# ESP-XBee_v1_0.net
KiCad netlist of a schematic drawn in EAGLE
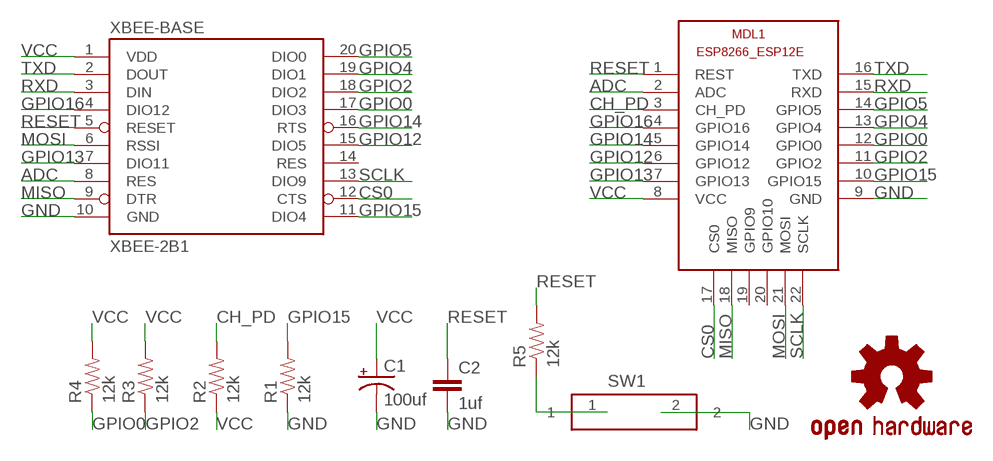
[diagram p0: schematic, sheet 1]

(export (version "E")
  (design (tool "Eeschema 10.0.6"))
  (components
    (comp (ref "C1")
      (value "100uf")
      (footprint "eagle-import:EIA3216-KIT")
      (libsource (lib "eagle-import") (part "CAP_POL1206-KIT"))
    )
    (comp (ref "C2")
      (value "1uf")
      (footprint "eagle-import:0805")
      (libsource (lib "eagle-import") (part "CAP0805"))
    )
    (comp (ref "LOGO3")
      (value "OSHW-LOGOS")
      (footprint "eagle-import:OSHW-LOGO-S")
      (libsource (lib "eagle-import") (part "OSHW-LOGOS"))
    )
    (comp (ref "MDL1")
      (value "ESP8266-12EESP8266-ESP12E")
      (footprint "eagle-import:ESP8266-ESP12E")
      (libsource (lib "eagle-import") (part "ESP8266-12EESP8266-ESP12E"))
    )
    (comp (ref "R1")
      (value "12k")
      (footprint "eagle-import:0805")
      (libsource (lib "eagle-import") (part "RESISTOR0805-RES"))
    )
    (comp (ref "R2")
      (value "12k")
      (footprint "eagle-import:0805")
      (libsource (lib "eagle-import") (part "RESISTOR0805-RES"))
    )
    (comp (ref "R3")
      (value "12k")
      (footprint "eagle-import:0805")
      (libsource (lib "eagle-import") (part "RESISTOR0805-RES"))
    )
    (comp (ref "R4")
      (value "12k")
      (footprint "eagle-import:0805")
      (libsource (lib "eagle-import") (part "RESISTOR0805-RES"))
    )
    (comp (ref "R5")
      (value "12k")
      (footprint "eagle-import:0805")
      (libsource (lib "eagle-import") (part "RESISTOR0805-RES"))
    )
    (comp (ref "SW1")
      (value "434111043826")
      (footprint "eagle-import:434111043826")
      (libsource (lib "eagle-import") (part "434111043826"))
    )
    (comp (ref "XBEE-BASE")
      (value "XBEE-2B1")
      (footprint "eagle-import:XBEE-1")
      (libsource (lib "eagle-import") (part "XBEE-2B1"))
    )
  )
  (nets
    (net (code "1") (name "/ADC") (class "Default")
      (node (ref "MDL1") (pin "2") (pinfunction "ADC_2") (pintype "bidirectional"))
      (node (ref "XBEE-BASE") (pin "8") (pinfunction "RES_8") (pintype "bidirectional"))
    )
    (net (code "2") (name "/CH_PD") (class "Default")
      (node (ref "MDL1") (pin "3") (pinfunction "CH_PD_3") (pintype "bidirectional"))
      (node (ref "R2") (pin "2") (pinfunction "2_2") (pintype "passive"))
    )
    (net (code "3") (name "/CS0") (class "Default")
      (node (ref "MDL1") (pin "17") (pinfunction "CS0_17") (pintype "bidirectional"))
      (node (ref "XBEE-BASE") (pin "12") (pinfunction "CTS_12") (pintype "output"))
    )
    (net (code "4") (name "/GND") (class "Default")
      (node (ref "C1") (pin "C") (pinfunction "-_C") (pintype "passive"))
      (node (ref "C2") (pin "2") (pinfunction "2_2") (pintype "passive"))
      (node (ref "MDL1") (pin "9") (pinfunction "GND_9") (pintype "bidirectional"))
      (node (ref "R1") (pin "1") (pinfunction "1_1") (pintype "passive"))
      (node (ref "SW1") (pin "2") (pinfunction "2_2") (pintype "bidirectional"))
      (node (ref "XBEE-BASE") (pin "10") (pinfunction "GND_10") (pintype "power_in"))
    )
    (net (code "5") (name "/GPIO0") (class "Default")
      (node (ref "MDL1") (pin "12") (pinfunction "GPIO0_12") (pintype "bidirectional"))
      (node (ref "R4") (pin "1") (pinfunction "1_1") (pintype "passive"))
      (node (ref "XBEE-BASE") (pin "17") (pinfunction "DIO3_17") (pintype "bidirectional"))
    )
    (net (code "6") (name "/GPIO2") (class "Default")
      (node (ref "MDL1") (pin "11") (pinfunction "GPIO2_11") (pintype "bidirectional"))
      (node (ref "R3") (pin "1") (pinfunction "1_1") (pintype "passive"))
      (node (ref "XBEE-BASE") (pin "18") (pinfunction "DIO2_18") (pintype "bidirectional"))
    )
    (net (code "7") (name "/GPIO4") (class "Default")
      (node (ref "MDL1") (pin "13") (pinfunction "GPIO4_13") (pintype "bidirectional"))
      (node (ref "XBEE-BASE") (pin "19") (pinfunction "DIO1_19") (pintype "bidirectional"))
    )
    (net (code "8") (name "/GPIO5") (class "Default")
      (node (ref "MDL1") (pin "14") (pinfunction "GPIO5_14") (pintype "bidirectional"))
      (node (ref "XBEE-BASE") (pin "20") (pinfunction "DIO0_20") (pintype "bidirectional"))
    )
    (net (code "9") (name "/GPIO12") (class "Default")
      (node (ref "MDL1") (pin "6") (pinfunction "GPIO12_6") (pintype "bidirectional"))
      (node (ref "XBEE-BASE") (pin "15") (pinfunction "DIO5_15") (pintype "bidirectional"))
    )
    (net (code "10") (name "/GPIO13") (class "Default")
      (node (ref "MDL1") (pin "7") (pinfunction "GPIO13_7") (pintype "bidirectional"))
      (node (ref "XBEE-BASE") (pin "7") (pinfunction "DIO11_7") (pintype "bidirectional"))
    )
    (net (code "11") (name "/GPIO14") (class "Default")
      (node (ref "MDL1") (pin "5") (pinfunction "GPIO14_5") (pintype "bidirectional"))
      (node (ref "XBEE-BASE") (pin "16") (pinfunction "RTS_16") (pintype "input"))
    )
    (net (code "12") (name "/GPIO15") (class "Default")
      (node (ref "MDL1") (pin "10") (pinfunction "GPIO15_10") (pintype "bidirectional"))
      (node (ref "R1") (pin "2") (pinfunction "2_2") (pintype "passive"))
      (node (ref "XBEE-BASE") (pin "11") (pinfunction "DIO4_11") (pintype "bidirectional"))
    )
    (net (code "13") (name "/GPIO16") (class "Default")
      (node (ref "MDL1") (pin "4") (pinfunction "GPIO16_4") (pintype "bidirectional"))
      (node (ref "XBEE-BASE") (pin "4") (pinfunction "DIO12_4") (pintype "bidirectional"))
    )
    (net (code "14") (name "/MISO") (class "Default")
      (node (ref "MDL1") (pin "18") (pinfunction "MISO_18") (pintype "bidirectional"))
      (node (ref "XBEE-BASE") (pin "9") (pinfunction "DTR_9") (pintype "bidirectional"))
    )
    (net (code "15") (name "/MOSI") (class "Default")
      (node (ref "MDL1") (pin "21") (pinfunction "MOSI_21") (pintype "bidirectional"))
      (node (ref "XBEE-BASE") (pin "6") (pinfunction "RSSI_6") (pintype "bidirectional"))
    )
    (net (code "16") (name "/RESET") (class "Default")
      (node (ref "C2") (pin "1") (pinfunction "1_1") (pintype "passive"))
      (node (ref "MDL1") (pin "1") (pinfunction "REST_1") (pintype "bidirectional"))
      (node (ref "R5") (pin "2") (pinfunction "2_2") (pintype "passive"))
      (node (ref "XBEE-BASE") (pin "5") (pinfunction "RESET_5") (pintype "input"))
    )
    (net (code "17") (name "/RXD") (class "Default")
      (node (ref "MDL1") (pin "15") (pinfunction "RXD_15") (pintype "bidirectional"))
      (node (ref "XBEE-BASE") (pin "3") (pinfunction "DIN_3") (pintype "input"))
    )
    (net (code "18") (name "/SCLK") (class "Default")
      (node (ref "MDL1") (pin "22") (pinfunction "SCLK_22") (pintype "bidirectional"))
      (node (ref "XBEE-BASE") (pin "13") (pinfunction "DIO9_13") (pintype "bidirectional"))
    )
    (net (code "19") (name "/TXD") (class "Default")
      (node (ref "MDL1") (pin "16") (pinfunction "TXD_16") (pintype "bidirectional"))
      (node (ref "XBEE-BASE") (pin "2") (pinfunction "DOUT_2") (pintype "output"))
    )
    (net (code "20") (name "/VCC") (class "Default")
      (node (ref "C1") (pin "A") (pinfunction "+_A") (pintype "passive"))
      (node (ref "MDL1") (pin "8") (pinfunction "VCC_8") (pintype "bidirectional"))
      (node (ref "R2") (pin "1") (pinfunction "1_1") (pintype "passive"))
      (node (ref "R3") (pin "2") (pinfunction "2_2") (pintype "passive"))
      (node (ref "R4") (pin "2") (pinfunction "2_2") (pintype "passive"))
      (node (ref "XBEE-BASE") (pin "1") (pinfunction "VDD_1") (pintype "power_in"))
    )
    (net (code "21") (name "Net-(R5-Pad1)") (class "Default")
      (node (ref "R5") (pin "1") (pinfunction "1_1") (pintype "passive"))
      (node (ref "SW1") (pin "1") (pinfunction "1_1") (pintype "bidirectional"))
    )
    (net (code "22") (name "unconnected-(MDL1-GPIO9-Pad19)") (class "Default")
      (node (ref "MDL1") (pin "19") (pinfunction "GPIO9_19") (pintype "bidirectional"))
    )
    (net (code "23") (name "unconnected-(MDL1-GPIO10-Pad20)") (class "Default")
      (node (ref "MDL1") (pin "20") (pinfunction "GPIO10_20") (pintype "bidirectional"))
    )
    (net (code "24") (name "unconnected-(XBEE-BASE-RES-Pad14)") (class "Default")
      (node (ref "XBEE-BASE") (pin "14") (pinfunction "RES_14") (pintype "bidirectional"))
    )
  )
)
